# power.net
KiCad netlist of a schematic drawn in Altium Designer
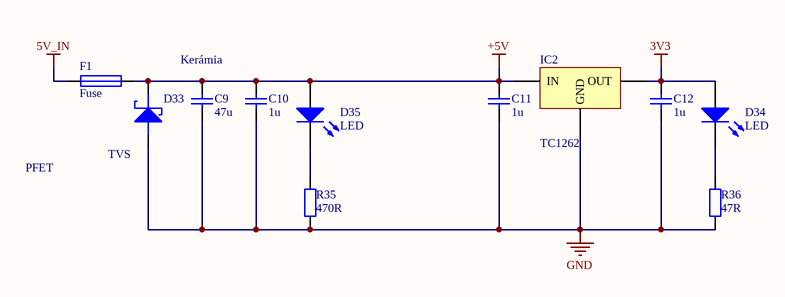
[diagram p0: power.SchDoc]

(export (version "E")
  (design (tool "Eeschema 10.0.6"))
  (components
    (comp (ref "C9")
      (value "47u")
      (footprint "FP_0805_CAP_085")
      (description "Capacitor")
      (libsource (lib "hallglib") (part "CAP"))
    )
    (comp (ref "C10")
      (value "1u")
      (footprint "FP_0805_CAP_085")
      (description "Capacitor")
      (libsource (lib "hallglib") (part "CAP"))
    )
    (comp (ref "C11")
      (value "1u")
      (footprint "FP_0805_CAP_085")
      (description "Capacitor")
      (libsource (lib "hallglib") (part "CAP"))
    )
    (comp (ref "C12")
      (value "1u")
      (footprint "FP_0805_CAP_085")
      (description "Capacitor")
      (libsource (lib "hallglib") (part "CAP"))
    )
    (comp (ref "D33")
      (value "TVS")
      (footprint "FP_SMB")
      (description "TVS diode")
      (libsource (lib "hallglib") (part "SCHOTTKY"))
    )
    (comp (ref "D34")
      (value "LED")
      (footprint "FP_0805_LED_GREEN")
      (description "Typical RED GaAs LED")
      (libsource (lib "hallglib") (part "LED"))
    )
    (comp (ref "D35")
      (value "LED")
      (footprint "FP_0805_LED_GREEN")
      (description "Typical RED GaAs LED")
      (libsource (lib "hallglib") (part "LED"))
    )
    (comp (ref "F1") (value "Fuse") (footprint "FP_MULTIFUSE") (libsource (lib "hallglib") (part "Fuse")))
    (comp (ref "IC2")
      (value "TC1262")
      (footprint "FP_SOT223")
      (description "Fixed LDO Voltage Regulator")
      (libsource (lib "mb") (part "TC1262"))
    )
    (comp (ref "R35")
      (value "470R")
      (footprint "FP_0805_RES")
      (description "Resistor")
      (libsource (lib "hallglib") (part "RES"))
    )
    (comp (ref "R36")
      (value "47R")
      (footprint "FP_0805_RES")
      (description "Resistor")
      (libsource (lib "hallglib") (part "RES"))
    )
  )
  (nets
    (net (code "1") (name "+5V") (class "Default")
      (node (ref "C10") (pin "2") (pinfunction "2_2") (pintype "passive"))
      (node (ref "C11") (pin "2") (pinfunction "2_2") (pintype "passive"))
      (node (ref "C9") (pin "2") (pinfunction "2_2") (pintype "passive"))
      (node (ref "D33") (pin "1") (pinfunction "CATHODE_1") (pintype "passive"))
      (node (ref "D35") (pin "1") (pinfunction "A_1") (pintype "passive"))
      (node (ref "F1") (pin "2") (pinfunction "2_2") (pintype "passive"))
      (node (ref "IC2") (pin "1") (pinfunction "IN_1") (pintype "passive"))
    )
    (net (code "2") (name "3V3") (class "Default")
      (node (ref "C12") (pin "2") (pinfunction "2_2") (pintype "passive"))
      (node (ref "D34") (pin "1") (pinfunction "A_1") (pintype "passive"))
      (node (ref "IC2") (pin "3") (pinfunction "OUT_3") (pintype "passive"))
    )
    (net (code "3") (name "5V_IN") (class "Default")
      (node (ref "F1") (pin "1") (pinfunction "1_1") (pintype "passive"))
    )
    (net (code "4") (name "GND") (class "Default")
      (node (ref "C10") (pin "1") (pinfunction "1_1") (pintype "passive"))
      (node (ref "C11") (pin "1") (pinfunction "1_1") (pintype "passive"))
      (node (ref "C12") (pin "1") (pinfunction "1_1") (pintype "passive"))
      (node (ref "C9") (pin "1") (pinfunction "1_1") (pintype "passive"))
      (node (ref "D33") (pin "2") (pinfunction "ANODE_2") (pintype "passive"))
      (node (ref "IC2") (pin "2") (pinfunction "GND_2") (pintype "passive"))
      (node (ref "R35") (pin "1") (pinfunction "1_1") (pintype "passive"))
      (node (ref "R36") (pin "1") (pinfunction "1_1") (pintype "passive"))
    )
    (net (code "5") (name "Net-(D34-K)") (class "Default")
      (node (ref "D34") (pin "2") (pinfunction "K_2") (pintype "passive"))
      (node (ref "R36") (pin "2") (pinfunction "2_2") (pintype "passive"))
    )
    (net (code "6") (name "Net-(D35-K)") (class "Default")
      (node (ref "D35") (pin "2") (pinfunction "K_2") (pintype "passive"))
      (node (ref "R35") (pin "2") (pinfunction "2_2") (pintype "passive"))
    )
  )
)
